# SparkFun_Motor_Driver-TB6612FNG.net
KiCad netlist of a schematic drawn in EAGLE
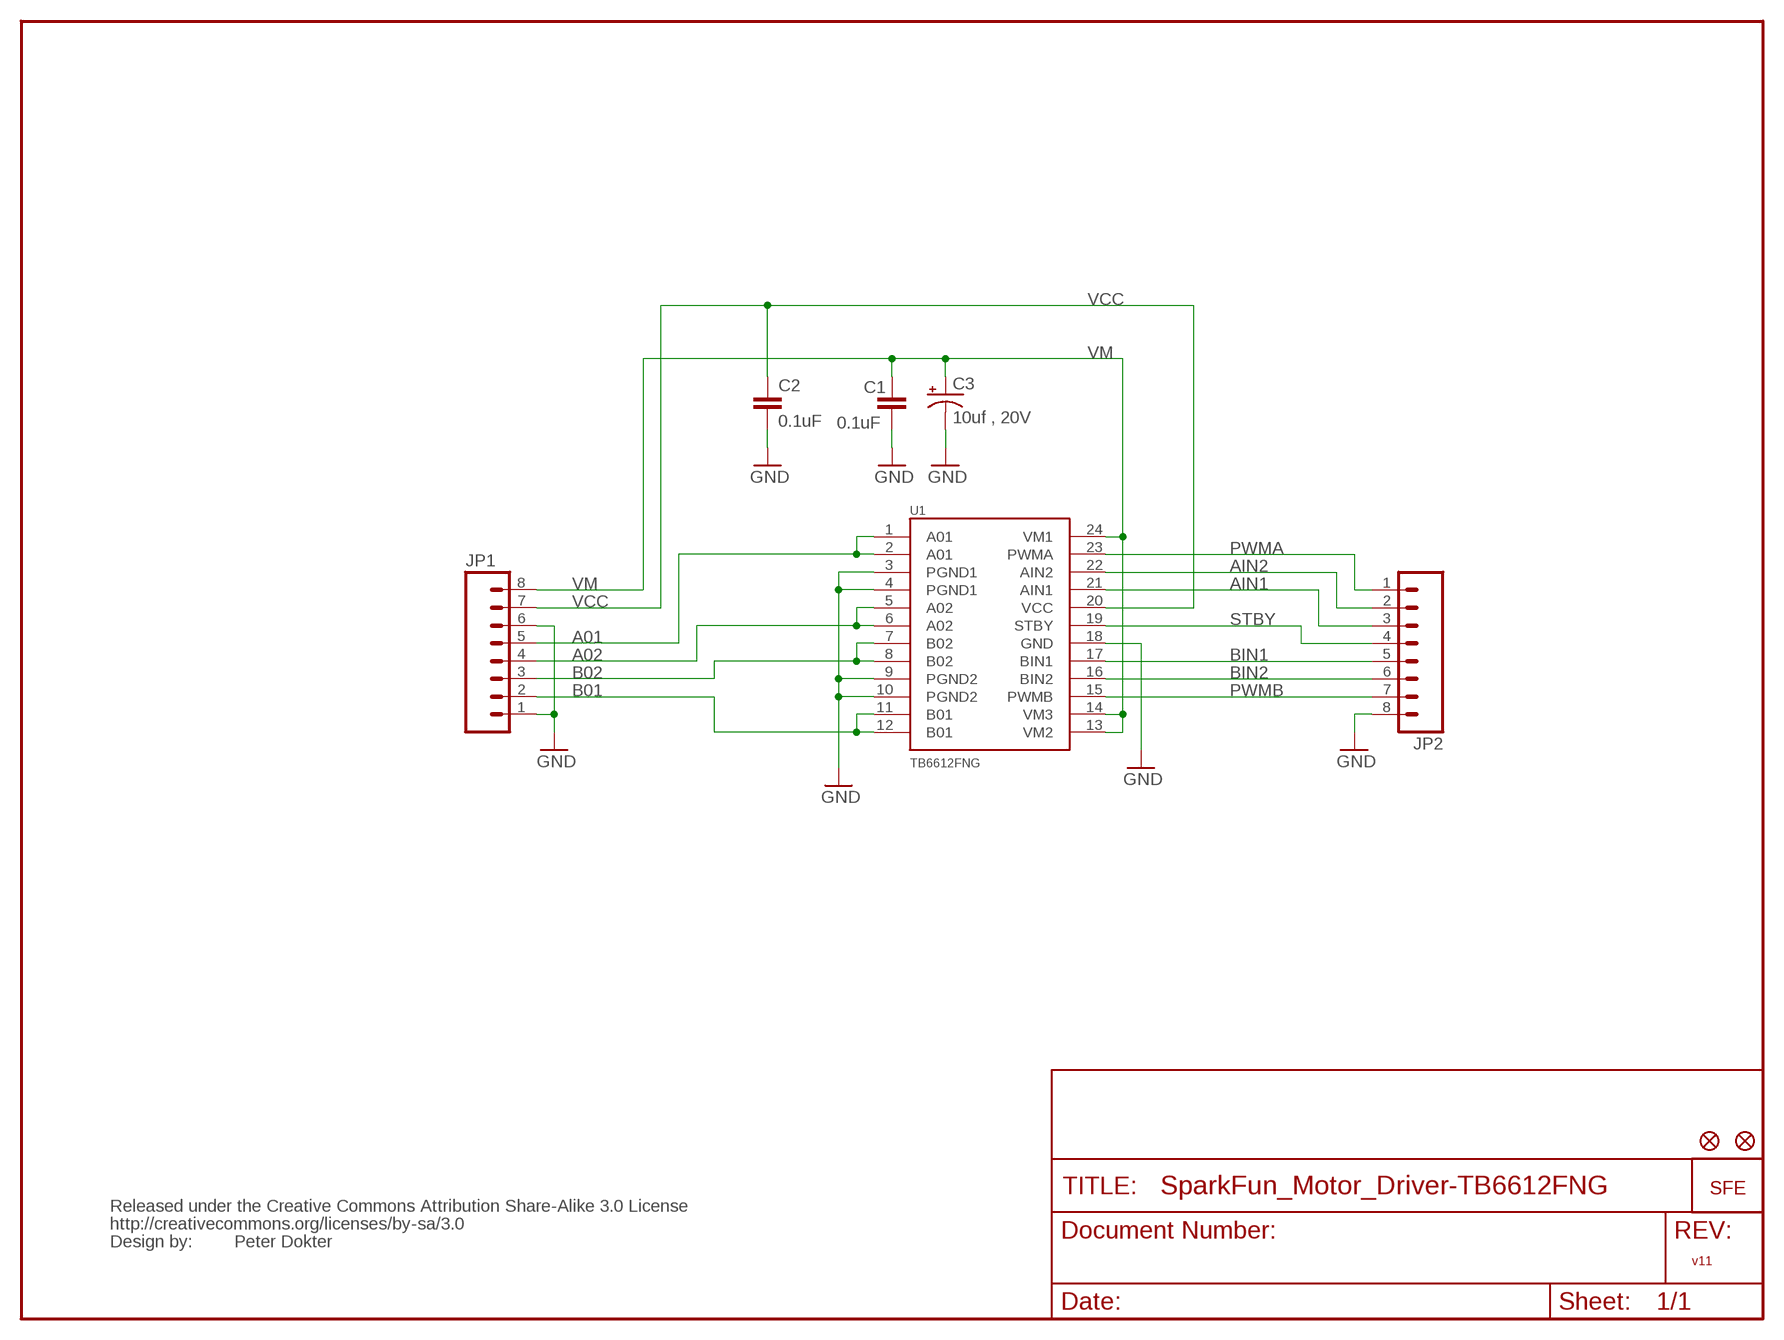
[diagram p0: schematic, sheet 1]

(export (version "E")
  (design (tool "Eeschema 10.0.6"))
  (components
    (comp (ref "C1")
      (value "0.1uF")
      (footprint "eagle-import:0402-CAP")
      (libsource (lib "eagle-import") (part "CAP0402-CAP"))
    )
    (comp (ref "C2")
      (value "0.1uF")
      (footprint "eagle-import:0402-CAP")
      (libsource (lib "eagle-import") (part "CAP0402-CAP"))
    )
    (comp (ref "C3")
      (value "10uf , 20V")
      (footprint "eagle-import:EIA3528")
      (libsource (lib "eagle-import") (part "CAP_POL3528"))
    )
    (comp (ref "JP1")
      (value "M08LONGPADS")
      (footprint "eagle-import:1X08_LONGPADS")
      (libsource (lib "eagle-import") (part "M08LONGPADS"))
    )
    (comp (ref "JP2")
      (value "M08LONGPADS")
      (footprint "eagle-import:1X08_LONGPADS")
      (libsource (lib "eagle-import") (part "M08LONGPADS"))
    )
    (comp (ref "JP4")
      (value "LOGO-SFESK")
      (footprint "eagle-import:SFE-LOGO-FLAME")
      (libsource (lib "eagle-import") (part "LOGO-SFESK"))
    )
    (comp (ref "JP5")
      (value "FIDUCIAL1X2")
      (footprint "eagle-import:FIDUCIAL-1X2")
      (libsource (lib "eagle-import") (part "FIDUCIAL1X2"))
    )
    (comp (ref "JP6")
      (value "FIDUCIAL1X2")
      (footprint "eagle-import:FIDUCIAL-1X2")
      (libsource (lib "eagle-import") (part "FIDUCIAL1X2"))
    )
    (comp (ref "U$1")
      (value "CREATIVE_COMMONS")
      (footprint "eagle-import:CREATIVE_COMMONS")
      (libsource (lib "eagle-import") (part "CREATIVE_COMMONS"))
    )
    (comp (ref "U1")
      (value "TB6612FNG")
      (footprint "eagle-import:SSOP24")
      (libsource (lib "eagle-import") (part "TB6621FNG"))
    )
  )
  (nets
    (net (code "1") (name "/A01") (class "Default")
      (node (ref "JP1") (pin "5") (pinfunction "5_5") (pintype "passive"))
      (node (ref "U1") (pin "1") (pinfunction "A01_1") (pintype "bidirectional"))
      (node (ref "U1") (pin "2") (pinfunction "A01_2") (pintype "bidirectional"))
    )
    (net (code "2") (name "/A02") (class "Default")
      (node (ref "JP1") (pin "4") (pinfunction "4_4") (pintype "passive"))
      (node (ref "U1") (pin "5") (pinfunction "A02_5") (pintype "bidirectional"))
      (node (ref "U1") (pin "6") (pinfunction "A02_6") (pintype "bidirectional"))
    )
    (net (code "3") (name "/AIN1") (class "Default")
      (node (ref "JP2") (pin "3") (pinfunction "3_3") (pintype "passive"))
      (node (ref "U1") (pin "21") (pinfunction "AIN1_21") (pintype "bidirectional"))
    )
    (net (code "4") (name "/AIN2") (class "Default")
      (node (ref "JP2") (pin "2") (pinfunction "2_2") (pintype "passive"))
      (node (ref "U1") (pin "22") (pinfunction "AIN2_22") (pintype "bidirectional"))
    )
    (net (code "5") (name "/B01") (class "Default")
      (node (ref "JP1") (pin "2") (pinfunction "2_2") (pintype "passive"))
      (node (ref "U1") (pin "11") (pinfunction "B01_11") (pintype "bidirectional"))
      (node (ref "U1") (pin "12") (pinfunction "B01_12") (pintype "bidirectional"))
    )
    (net (code "6") (name "/B02") (class "Default")
      (node (ref "JP1") (pin "3") (pinfunction "3_3") (pintype "passive"))
      (node (ref "U1") (pin "7") (pinfunction "B02_7") (pintype "bidirectional"))
      (node (ref "U1") (pin "8") (pinfunction "B02_8") (pintype "bidirectional"))
    )
    (net (code "7") (name "/BIN1") (class "Default")
      (node (ref "JP2") (pin "5") (pinfunction "5_5") (pintype "passive"))
      (node (ref "U1") (pin "17") (pinfunction "BIN1_17") (pintype "bidirectional"))
    )
    (net (code "8") (name "/BIN2") (class "Default")
      (node (ref "JP2") (pin "6") (pinfunction "6_6") (pintype "passive"))
      (node (ref "U1") (pin "16") (pinfunction "BIN2_16") (pintype "bidirectional"))
    )
    (net (code "9") (name "/PWMA") (class "Default")
      (node (ref "JP2") (pin "1") (pinfunction "1_1") (pintype "passive"))
      (node (ref "U1") (pin "23") (pinfunction "PWMA_23") (pintype "bidirectional"))
    )
    (net (code "10") (name "/PWMB") (class "Default")
      (node (ref "JP2") (pin "7") (pinfunction "7_7") (pintype "passive"))
      (node (ref "U1") (pin "15") (pinfunction "PWMB_15") (pintype "bidirectional"))
    )
    (net (code "11") (name "/STBY") (class "Default")
      (node (ref "JP2") (pin "4") (pinfunction "4_4") (pintype "passive"))
      (node (ref "U1") (pin "19") (pinfunction "STBY_19") (pintype "bidirectional"))
    )
    (net (code "12") (name "/VCC") (class "Default")
      (node (ref "C2") (pin "1") (pinfunction "1_1") (pintype "passive"))
      (node (ref "JP1") (pin "7") (pinfunction "7_7") (pintype "passive"))
      (node (ref "U1") (pin "20") (pinfunction "VCC_20") (pintype "bidirectional"))
    )
    (net (code "13") (name "/VM") (class "Default")
      (node (ref "C1") (pin "1") (pinfunction "1_1") (pintype "passive"))
      (node (ref "C3") (pin "A") (pinfunction "+_A") (pintype "passive"))
      (node (ref "JP1") (pin "8") (pinfunction "8_8") (pintype "passive"))
      (node (ref "U1") (pin "13") (pinfunction "VM2_13") (pintype "bidirectional"))
      (node (ref "U1") (pin "14") (pinfunction "VM3_14") (pintype "bidirectional"))
      (node (ref "U1") (pin "24") (pinfunction "VM1_24") (pintype "bidirectional"))
    )
    (net (code "14") (name "GND") (class "Default")
      (node (ref "C1") (pin "2") (pinfunction "2_2") (pintype "passive"))
      (node (ref "C2") (pin "2") (pinfunction "2_2") (pintype "passive"))
      (node (ref "C3") (pin "C") (pinfunction "-_C") (pintype "passive"))
      (node (ref "JP1") (pin "1") (pinfunction "1_1") (pintype "passive"))
      (node (ref "JP1") (pin "6") (pinfunction "6_6") (pintype "passive"))
      (node (ref "JP2") (pin "8") (pinfunction "8_8") (pintype "passive"))
      (node (ref "U1") (pin "10") (pinfunction "PGND2_10") (pintype "bidirectional"))
      (node (ref "U1") (pin "18") (pinfunction "GND_18") (pintype "bidirectional"))
      (node (ref "U1") (pin "3") (pinfunction "PGND1_3") (pintype "bidirectional"))
      (node (ref "U1") (pin "4") (pinfunction "PGND1_4") (pintype "bidirectional"))
      (node (ref "U1") (pin "9") (pinfunction "PGND2_9") (pintype "bidirectional"))
    )
  )
)
